# MCU.net
KiCad netlist of a schematic drawn in Altium Designer
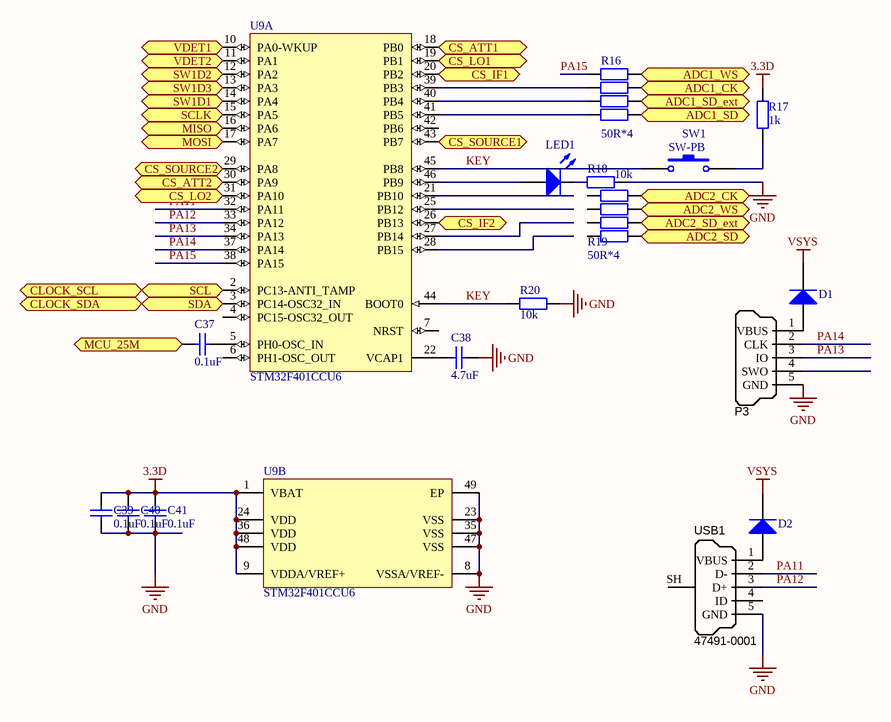
[diagram p0: MCU.SchDoc]

(export (version "E")
  (design (tool "Eeschema 10.0.6"))
  (components
    (comp (ref "C37")
      (value "0.1uF")
      (footprint "0402")
      (description "Capacitor")
      (fields (field (name "Comment") "Cap") (field (name "PUBLISHER") "Altium Limited"))
      (libsource (lib "RTC6705") (part "Cap"))
    )
    (comp (ref "C38")
      (value "4.7uF")
      (footprint "0603L")
      (description "Capacitor")
      (fields (field (name "Comment") "Cap") (field (name "PUBLISHER") "Altium Limited"))
      (libsource (lib "RTC6705") (part "Cap"))
    )
    (comp (ref "C39")
      (value "0.1uF")
      (footprint "0402")
      (description "Capacitor")
      (fields (field (name "Comment") "Cap") (field (name "PUBLISHER") "Altium Limited"))
      (libsource (lib "RTC6705") (part "Cap"))
    )
    (comp (ref "C40")
      (value "0.1uF")
      (footprint "0402")
      (description "Capacitor")
      (fields (field (name "Comment") "Cap") (field (name "PUBLISHER") "Altium Limited"))
      (libsource (lib "RTC6705") (part "Cap"))
    )
    (comp (ref "C41")
      (value "0.1uF")
      (footprint "0402")
      (description "Capacitor")
      (fields (field (name "Comment") "Cap") (field (name "PUBLISHER") "Altium Limited"))
      (libsource (lib "RTC6705") (part "Cap"))
    )
    (comp (ref "D1")
      (value "~")
      (footprint "LC-SOD-323")
      (description "High Conductance Fast Diode")
      (fields (field (name "PUBLISHER") "Altium Limited"))
      (libsource (lib "Miscellaneous Devices") (part "Diode 1N4148"))
    )
    (comp (ref "D2")
      (value "~")
      (footprint "LC-SOD-323")
      (description "High Conductance Fast Diode")
      (fields (field (name "PUBLISHER") "Altium Limited"))
      (libsource (lib "Miscellaneous Devices") (part "Diode 1N4148"))
    )
    (comp (ref "LED1")
      (value "LED0")
      (footprint "0603")
      (description "Typical INFRARED GaAs LED")
      (fields (field (name "PUBLISHER") "Altium Limited"))
      (libsource (lib "Miscellaneous Devices") (part "LED0"))
    )
    (comp (ref "P3")
      (value "SWD_MicroUSB")
      (footprint "MICRO-YZX")
      (description "Connector SMD USB Micro Type B middle mount")
      (libsource (lib "sch") (part "SWD_MicroUSB"))
    )
    (comp (ref "R16")
      (value "50R*4")
      (footprint "0402X4")
      (description "Resistor")
      (fields (field (name "PUBLISHER") "Altium Limited"))
      (libsource (lib "sch") (part "Res*4"))
    )
    (comp (ref "R17")
      (value "1k")
      (footprint "0402")
      (description "Resistor")
      (fields (field (name "PUBLISHER") "Altium Limited"))
      (libsource (lib "Miscellaneous Devices") (part "Res2"))
    )
    (comp (ref "R18")
      (value "10k")
      (footprint "0402")
      (description "Resistor")
      (fields (field (name "PUBLISHER") "Altium Limited"))
      (libsource (lib "") (part "Res2_1"))
    )
    (comp (ref "R19")
      (value "50R*4")
      (footprint "0402X4")
      (description "Resistor")
      (fields (field (name "PUBLISHER") "Altium Limited"))
      (libsource (lib "sch") (part "Res*4"))
    )
    (comp (ref "R20")
      (value "10k")
      (footprint "0402")
      (description "Resistor")
      (fields (field (name "Comment") "Res2") (field (name "PUBLISHER") "Altium Limited"))
      (libsource (lib "RTC6705") (part "Res2"))
    )
    (comp (ref "SW1")
      (value "SW-PB")
      (footprint "SW3x4")
      (description "Switch")
      (fields (field (name "PUBLISHER") "Altium Limited"))
      (libsource (lib "Miscellaneous Devices") (part "SW-PB"))
    )
    (comp (ref "U9")
      (value "STM32F401CCU6")
      (footprint "STM-UFQFPN48_N")
      (fields (field (name "MANUFACTURER") "STMicroelectronics"))
      (libsource (lib "STMicroelectronics STM32 F4") (part "STM32F401CCU6"))
    )
    (comp (ref "USB1")
      (value "USB Micro Type B")
      (footprint "MICRO-YZX")
      (description "Connector SMD USB Micro Type B middle mount")
      (fields (field (name "MANUFACTURER PART NUMBER 1") "47491-0001"))
      (libsource (lib "PBL - Connectors") (part "USB_Micro_TypeB"))
    )
  )
  (nets
    (net (code "1") (name "/ADC1_CK") (class "Default")
      (node (ref "R16") (pin "2") (pinfunction "2_2") (pintype "passive"))
    )
    (net (code "4") (name "/ADC1_SD") (class "Default")
      (node (ref "R16") (pin "4") (pinfunction "4_4") (pintype "passive"))
    )
    (net (code "5") (name "/ADC1_SD_ext") (class "Default")
      (node (ref "R16") (pin "3") (pinfunction "3_3") (pintype "passive"))
    )
    (net (code "8") (name "/ADC1_WS") (class "Default")
      (node (ref "R16") (pin "1") (pinfunction "1_1") (pintype "passive"))
    )
    (net (code "12") (name "/ADC2_CK") (class "Default")
      (node (ref "R19") (pin "1") (pinfunction "1_1") (pintype "passive"))
    )
    (net (code "16") (name "/ADC2_SD") (class "Default")
      (node (ref "R19") (pin "4") (pinfunction "4_4") (pintype "passive"))
    )
    (net (code "18") (name "/ADC2_SD_ext") (class "Default")
      (node (ref "R19") (pin "3") (pinfunction "3_3") (pintype "passive"))
    )
    (net (code "19") (name "/ADC2_WS") (class "Default")
      (node (ref "R19") (pin "2") (pinfunction "2_2") (pintype "passive"))
    )
    (net (code "20") (name "/CS_ATT1") (class "Default")
      (node (ref "U9") (pin "18") (pinfunction "PB0_18") (pintype "bidirectional"))
    )
    (net (code "21") (name "/CS_ATT2") (class "Default")
      (node (ref "U9") (pin "30") (pinfunction "PA9_30") (pintype "bidirectional"))
    )
    (net (code "22") (name "/CS_IF1") (class "Default")
      (node (ref "U9") (pin "20") (pinfunction "PB2_20") (pintype "bidirectional"))
    )
    (net (code "23") (name "/CS_IF2") (class "Default")
      (node (ref "U9") (pin "26") (pinfunction "PB13_26") (pintype "bidirectional"))
    )
    (net (code "24") (name "/CS_LO1") (class "Default")
      (node (ref "U9") (pin "19") (pinfunction "PB1_19") (pintype "bidirectional"))
    )
    (net (code "25") (name "/CS_LO2") (class "Default")
      (node (ref "U9") (pin "31") (pinfunction "PA10_31") (pintype "bidirectional"))
    )
    (net (code "26") (name "/CS_SOURCE1") (class "Default")
      (node (ref "U9") (pin "43") (pinfunction "PB7_43") (pintype "bidirectional"))
    )
    (net (code "27") (name "/CS_SOURCE2") (class "Default")
      (node (ref "U9") (pin "29") (pinfunction "PA8_29") (pintype "bidirectional"))
    )
    (net (code "28") (name "/KEY") (class "Default")
      (node (ref "R20") (pin "1") (pinfunction "1_1") (pintype "passive"))
      (node (ref "SW1") (pin "1") (pinfunction "1_1") (pintype "passive"))
      (node (ref "U9") (pin "44") (pinfunction "BOOT0_44") (pintype "input"))
      (node (ref "U9") (pin "45") (pinfunction "PB8_45") (pintype "bidirectional"))
    )
    (net (code "29") (name "/MCU_25M") (class "Default")
      (node (ref "C37") (pin "2") (pinfunction "2_2") (pintype "passive"))
    )
    (net (code "30") (name "/MISO") (class "Default")
      (node (ref "U9") (pin "16") (pinfunction "PA6_16") (pintype "bidirectional"))
    )
    (net (code "31") (name "/MOSI") (class "Default")
      (node (ref "U9") (pin "17") (pinfunction "PA7_17") (pintype "bidirectional"))
    )
    (net (code "32") (name "/PA11") (class "Default")
      (node (ref "U9") (pin "32") (pinfunction "PA11_32") (pintype "bidirectional"))
      (node (ref "USB1") (pin "2") (pinfunction "D-_2") (pintype "passive"))
    )
    (net (code "33") (name "/PA12") (class "Default")
      (node (ref "U9") (pin "33") (pinfunction "PA12_33") (pintype "bidirectional"))
      (node (ref "USB1") (pin "3") (pinfunction "D+_3") (pintype "passive"))
    )
    (net (code "34") (name "/PA13") (class "Default")
      (node (ref "P3") (pin "3") (pinfunction "IO_3") (pintype "passive"))
      (node (ref "U9") (pin "34") (pinfunction "PA13_34") (pintype "bidirectional"))
    )
    (net (code "35") (name "/PA14") (class "Default")
      (node (ref "P3") (pin "2") (pinfunction "CLK_2") (pintype "passive"))
      (node (ref "U9") (pin "37") (pinfunction "PA14_37") (pintype "bidirectional"))
    )
    (net (code "36") (name "/PA15") (class "Default")
      (node (ref "R16") (pin "8") (pinfunction "8_8") (pintype "passive"))
      (node (ref "U9") (pin "38") (pinfunction "PA15_38") (pintype "bidirectional"))
    )
    (net (code "37") (name "/SCL") (class "Default")
      (node (ref "U9") (pin "2") (pinfunction "PC13-ANTI_TAMP_2") (pintype "bidirectional"))
    )
    (net (code "38") (name "/SCLK") (class "Default")
      (node (ref "U9") (pin "15") (pinfunction "PA5_15") (pintype "bidirectional"))
    )
    (net (code "39") (name "/SDA") (class "Default")
      (node (ref "U9") (pin "3") (pinfunction "PC14-OSC32_IN_3") (pintype "bidirectional"))
    )
    (net (code "40") (name "/SW1D1") (class "Default")
      (node (ref "U9") (pin "14") (pinfunction "PA4_14") (pintype "bidirectional"))
    )
    (net (code "41") (name "/SW1D2") (class "Default")
      (node (ref "U9") (pin "12") (pinfunction "PA2_12") (pintype "bidirectional"))
    )
    (net (code "42") (name "/SW1D3") (class "Default")
      (node (ref "U9") (pin "13") (pinfunction "PA3_13") (pintype "bidirectional"))
    )
    (net (code "43") (name "/VDET1") (class "Default")
      (node (ref "U9") (pin "10") (pinfunction "PA0-WKUP_10") (pintype "bidirectional"))
    )
    (net (code "44") (name "/VDET2") (class "Default")
      (node (ref "U9") (pin "11") (pinfunction "PA1_11") (pintype "bidirectional"))
    )
    (net (code "45") (name "3.3D") (class "Default")
      (node (ref "C39") (pin "2") (pinfunction "2_2") (pintype "passive"))
      (node (ref "C40") (pin "2") (pinfunction "2_2") (pintype "passive"))
      (node (ref "C41") (pin "2") (pinfunction "2_2") (pintype "passive"))
      (node (ref "R17") (pin "2") (pinfunction "2_2") (pintype "passive"))
      (node (ref "U9") (pin "1") (pinfunction "VBAT_1") (pintype "power_in"))
      (node (ref "U9") (pin "24") (pinfunction "VDD_24") (pintype "power_in"))
      (node (ref "U9") (pin "36") (pinfunction "VDD_36") (pintype "power_in"))
      (node (ref "U9") (pin "48") (pinfunction "VDD_48") (pintype "power_in"))
      (node (ref "U9") (pin "9") (pinfunction "VDDA/VREF+_9") (pintype "power_in"))
    )
    (net (code "46") (name "GND") (class "Default")
      (node (ref "C38") (pin "1") (pinfunction "1_1") (pintype "passive"))
      (node (ref "C39") (pin "1") (pinfunction "1_1") (pintype "passive"))
      (node (ref "C40") (pin "1") (pinfunction "1_1") (pintype "passive"))
      (node (ref "C41") (pin "1") (pinfunction "1_1") (pintype "passive"))
      (node (ref "P3") (pin "5") (pinfunction "GND_5") (pintype "passive"))
      (node (ref "R18") (pin "2") (pinfunction "2_2") (pintype "passive"))
      (node (ref "R20") (pin "2") (pinfunction "2_2") (pintype "passive"))
      (node (ref "U9") (pin "23") (pinfunction "VSS_23") (pintype "power_in"))
      (node (ref "U9") (pin "35") (pinfunction "VSS_35") (pintype "power_in"))
      (node (ref "U9") (pin "47") (pinfunction "VSS_47") (pintype "power_in"))
      (node (ref "U9") (pin "49") (pinfunction "EP_49") (pintype "power_in"))
      (node (ref "U9") (pin "8") (pinfunction "VSSA/VREF-_8") (pintype "power_in"))
      (node (ref "USB1") (pin "5") (pinfunction "GND_5") (pintype "passive"))
    )
    (net (code "47") (name "Net-(D1-A)") (class "Default")
      (node (ref "D1") (pin "1") (pinfunction "A_1") (pintype "passive"))
      (node (ref "P3") (pin "1") (pinfunction "VBUS_1") (pintype "passive"))
    )
    (net (code "48") (name "Net-(D2-A)") (class "Default")
      (node (ref "D2") (pin "1") (pinfunction "A_1") (pintype "passive"))
      (node (ref "USB1") (pin "1") (pinfunction "VBUS_1") (pintype "passive"))
    )
    (net (code "49") (name "Net-(LED1-A)") (class "Default")
      (node (ref "LED1") (pin "1") (pinfunction "A_1") (pintype "passive"))
      (node (ref "U9") (pin "46") (pinfunction "PB9_46") (pintype "bidirectional"))
    )
    (net (code "50") (name "Net-(LED1-K)") (class "Default")
      (node (ref "LED1") (pin "2") (pinfunction "K_2") (pintype "passive"))
      (node (ref "R18") (pin "1") (pinfunction "1_1") (pintype "passive"))
    )
    (net (code "51") (name "Net-(R17-Pad1)") (class "Default")
      (node (ref "R17") (pin "1") (pinfunction "1_1") (pintype "passive"))
      (node (ref "SW1") (pin "2") (pinfunction "2_2") (pintype "passive"))
    )
    (net (code "52") (name "Net-(U9A-PB3)") (class "Default")
      (node (ref "R16") (pin "7") (pinfunction "7_7") (pintype "passive"))
      (node (ref "U9") (pin "39") (pinfunction "PB3_39") (pintype "bidirectional"))
    )
    (net (code "53") (name "Net-(U9A-PB4)") (class "Default")
      (node (ref "R16") (pin "6") (pinfunction "6_6") (pintype "passive"))
      (node (ref "U9") (pin "40") (pinfunction "PB4_40") (pintype "bidirectional"))
    )
    (net (code "54") (name "Net-(U9A-PB5)") (class "Default")
      (node (ref "R16") (pin "5") (pinfunction "5_5") (pintype "passive"))
      (node (ref "U9") (pin "41") (pinfunction "PB5_41") (pintype "bidirectional"))
    )
    (net (code "55") (name "Net-(U9A-PH0-OSC_IN)") (class "Default")
      (node (ref "C37") (pin "1") (pinfunction "1_1") (pintype "passive"))
      (node (ref "U9") (pin "5") (pinfunction "PH0-OSC_IN_5") (pintype "bidirectional"))
    )
    (net (code "56") (name "Net-(U9A-VCAP1)") (class "Default")
      (node (ref "C38") (pin "2") (pinfunction "2_2") (pintype "passive"))
      (node (ref "U9") (pin "22") (pinfunction "VCAP1_22") (pintype "power_in"))
    )
    (net (code "57") (name "VSYS") (class "Default")
      (node (ref "D1") (pin "2") (pinfunction "K_2") (pintype "passive"))
      (node (ref "D2") (pin "2") (pinfunction "K_2") (pintype "passive"))
    )
    (net (code "58") (name "unconnected-(P3-SWO-Pad4)") (class "Default")
      (node (ref "P3") (pin "4") (pinfunction "SWO_4") (pintype "passive"))
    )
    (net (code "59") (name "unconnected-(R19-Pad5)") (class "Default")
      (node (ref "R19") (pin "5") (pinfunction "5_5") (pintype "passive"))
    )
    (net (code "60") (name "unconnected-(R19-Pad6)") (class "Default")
      (node (ref "R19") (pin "6") (pinfunction "6_6") (pintype "passive"))
    )
    (net (code "61") (name "unconnected-(R19-Pad7)") (class "Default")
      (node (ref "R19") (pin "7") (pinfunction "7_7") (pintype "passive"))
    )
    (net (code "62") (name "unconnected-(R19-Pad8)") (class "Default")
      (node (ref "R19") (pin "8") (pinfunction "8_8") (pintype "passive"))
    )
    (net (code "63") (name "unconnected-(U9A-NRST-Pad7)") (class "Default")
      (node (ref "U9") (pin "7") (pinfunction "NRST_7") (pintype "bidirectional"))
    )
    (net (code "64") (name "unconnected-(U9A-PB6-Pad42)") (class "Default")
      (node (ref "U9") (pin "42") (pinfunction "PB6_42") (pintype "bidirectional"))
    )
    (net (code "65") (name "unconnected-(U9A-PB10-Pad21)") (class "Default")
      (node (ref "U9") (pin "21") (pinfunction "PB10_21") (pintype "bidirectional"))
    )
    (net (code "66") (name "unconnected-(U9A-PB12-Pad25)") (class "Default")
      (node (ref "U9") (pin "25") (pinfunction "PB12_25") (pintype "bidirectional"))
    )
    (net (code "67") (name "unconnected-(U9A-PB14-Pad27)") (class "Default")
      (node (ref "U9") (pin "27") (pinfunction "PB14_27") (pintype "bidirectional"))
    )
    (net (code "68") (name "unconnected-(U9A-PB15-Pad28)") (class "Default")
      (node (ref "U9") (pin "28") (pinfunction "PB15_28") (pintype "bidirectional"))
    )
    (net (code "69") (name "unconnected-(U9A-PC15-OSC32_OUT-Pad4)") (class "Default")
      (node (ref "U9") (pin "4") (pinfunction "PC15-OSC32_OUT_4") (pintype "bidirectional"))
    )
    (net (code "70") (name "unconnected-(U9A-PH1-OSC_OUT-Pad6)") (class "Default")
      (node (ref "U9") (pin "6") (pinfunction "PH1-OSC_OUT_6") (pintype "bidirectional"))
    )
    (net (code "71") (name "unconnected-(USB1-ID-Pad4)") (class "Default")
      (node (ref "USB1") (pin "4") (pinfunction "ID_4") (pintype "passive"))
    )
    (net (code "72") (name "unconnected-(USB1-Shell-PadSH)") (class "Default")
      (node (ref "USB1") (pin "SH") (pinfunction "Shell_SH") (pintype "passive"))
    )
  )
)
